# BEP31_Test_Interface4_Seed.net
KiCad netlist of a schematic drawn in EAGLE
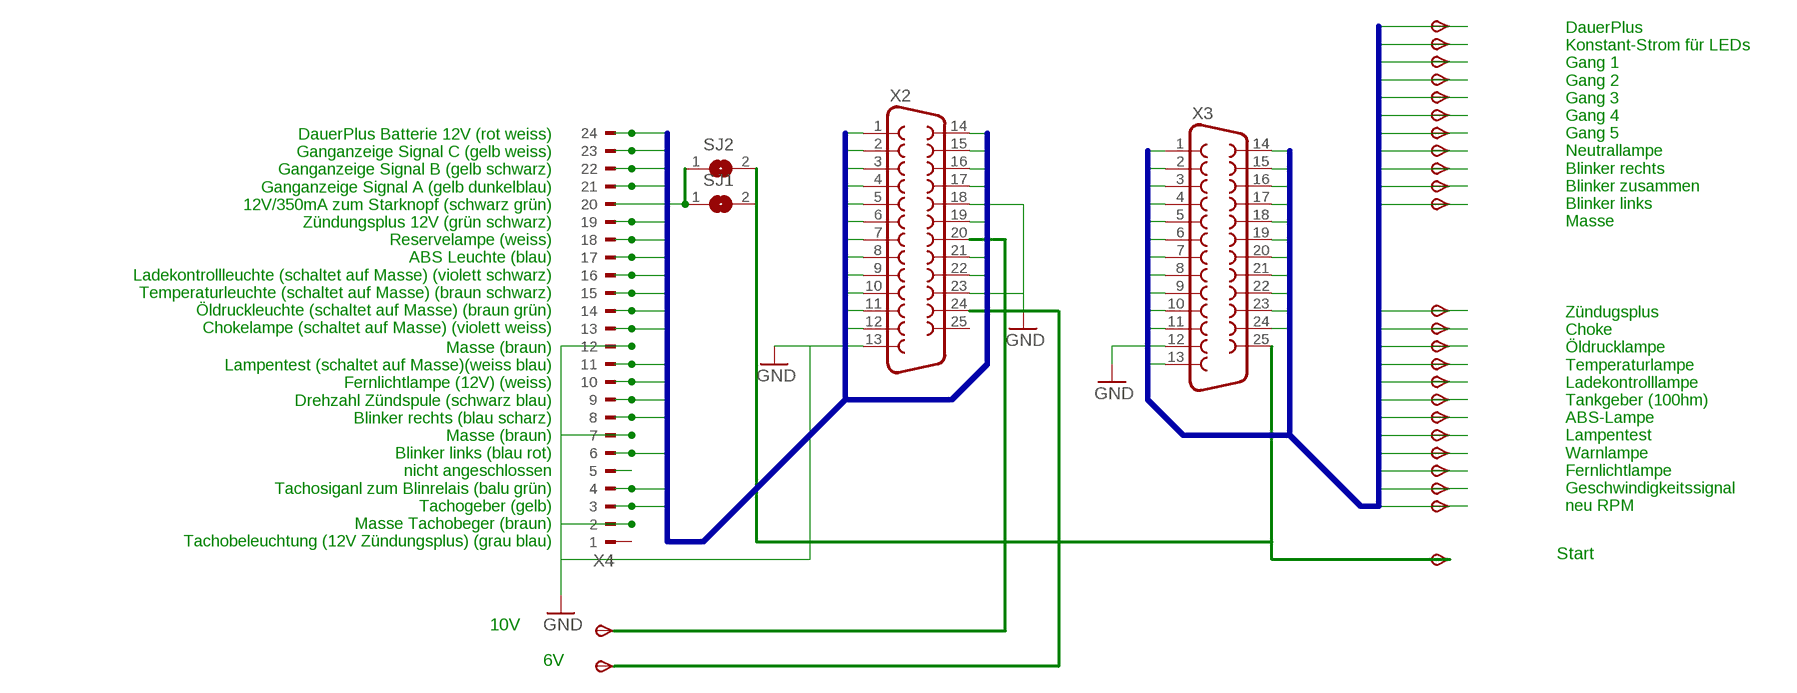
[diagram p0: schematic, sheet 1]
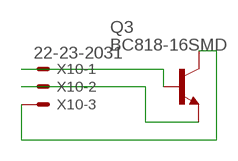
[diagram p1: schematic, sheet 2]
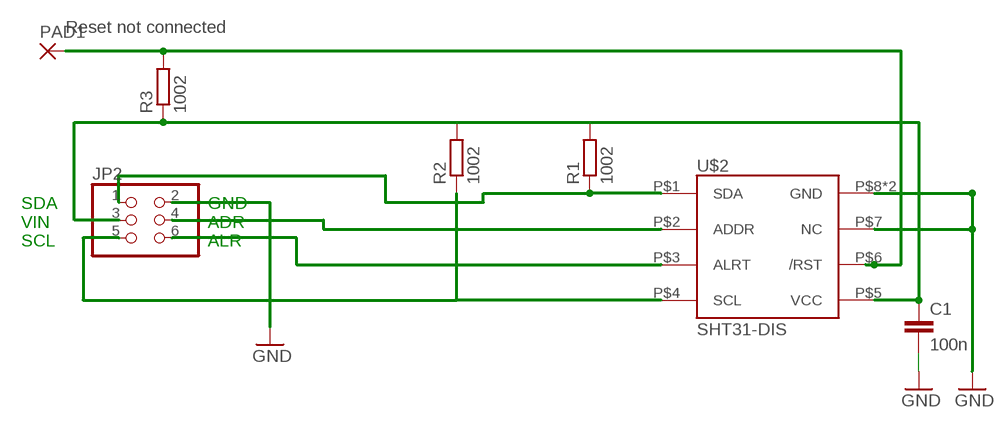
[diagram p2: schematic, sheet 3]

(export (version "E")
  (design (tool "Eeschema 10.0.6"))
  (components
    (comp (ref "Q3")
      (value "BC818-16SMD")
      (footprint "eagle-import:SOT23-BEC")
      (libsource (lib "eagle-import") (part "BC818SMD-16"))
    )
    (comp (ref "X10")
      (value "22-23-2031")
      (footprint "eagle-import:22-23-2031")
      (fields (field (name "MF") "MOLEX"))
      (libsource (lib "eagle-import") (part "22-23-2031"))
    )
    (comp (ref "C1")
      (value "100n")
      (footprint "eagle-import:C0805K")
      (libsource (lib "eagle-import") (part "C-EUC0805K"))
    )
    (comp (ref "JP2")
      (value "PINHD-2X3")
      (footprint "eagle-import:2X03")
      (libsource (lib "eagle-import") (part "PINHD-2X3"))
    )
    (comp (ref "PAD1")
      (value "1,6/0,8")
      (footprint "eagle-import:1,6_0,8")
      (libsource (lib "eagle-import") (part "1,6/0,8"))
    )
    (comp (ref "R1")
      (value "1002")
      (footprint "eagle-import:R0805")
      (libsource (lib "eagle-import") (part "R-EU_R0805"))
    )
    (comp (ref "R2")
      (value "1002")
      (footprint "eagle-import:R0805")
      (libsource (lib "eagle-import") (part "R-EU_R0805"))
    )
    (comp (ref "R3")
      (value "1002")
      (footprint "eagle-import:R0805")
      (libsource (lib "eagle-import") (part "R-EU_R0805"))
    )
    (comp (ref "U$2")
      (value "SHT31-DIS")
      (footprint "eagle-import:SHT3X")
      (libsource (lib "eagle-import") (part "SHT31-DIS"))
    )
    (comp (ref "SJ1") (value "SJ") (footprint "eagle-import:SJ") (libsource (lib "eagle-import") (part "SJ")))
    (comp (ref "SJ2") (value "SJ") (footprint "eagle-import:SJ") (libsource (lib "eagle-import") (part "SJ")))
    (comp (ref "TP1")
      (value "TPSFEDERPIN")
      (footprint "eagle-import:1,36ID")
      (libsource (lib "eagle-import") (part "TPSFEDERPIN"))
    )
    (comp (ref "TP2")
      (value "TPSFEDERPIN")
      (footprint "eagle-import:1,36ID")
      (libsource (lib "eagle-import") (part "TPSFEDERPIN"))
    )
    (comp (ref "TP3")
      (value "TPSFEDERPIN")
      (footprint "eagle-import:1,36ID")
      (libsource (lib "eagle-import") (part "TPSFEDERPIN"))
    )
    (comp (ref "TP4")
      (value "TPSFEDERPIN")
      (footprint "eagle-import:1,36ID")
      (libsource (lib "eagle-import") (part "TPSFEDERPIN"))
    )
    (comp (ref "TP5")
      (value "TPSFEDERPIN")
      (footprint "eagle-import:1,36ID")
      (libsource (lib "eagle-import") (part "TPSFEDERPIN"))
    )
    (comp (ref "TP6")
      (value "TPSFEDERPIN")
      (footprint "eagle-import:1,36ID")
      (libsource (lib "eagle-import") (part "TPSFEDERPIN"))
    )
    (comp (ref "TP7")
      (value "TPSFEDERPIN")
      (footprint "eagle-import:1,36ID")
      (libsource (lib "eagle-import") (part "TPSFEDERPIN"))
    )
    (comp (ref "TP8")
      (value "TPSFEDERPIN")
      (footprint "eagle-import:1,36ID")
      (libsource (lib "eagle-import") (part "TPSFEDERPIN"))
    )
    (comp (ref "TP9")
      (value "TPSFEDERPIN")
      (footprint "eagle-import:1,36ID")
      (libsource (lib "eagle-import") (part "TPSFEDERPIN"))
    )
    (comp (ref "TP10")
      (value "TPSFEDERPIN")
      (footprint "eagle-import:1,36ID")
      (libsource (lib "eagle-import") (part "TPSFEDERPIN"))
    )
    (comp (ref "TP11")
      (value "TPSFEDERPIN")
      (footprint "eagle-import:1,36ID")
      (libsource (lib "eagle-import") (part "TPSFEDERPIN"))
    )
    (comp (ref "TP12")
      (value "TPSFEDERPIN")
      (footprint "eagle-import:1,36ID")
      (libsource (lib "eagle-import") (part "TPSFEDERPIN"))
    )
    (comp (ref "TP13")
      (value "TPSFEDERPIN")
      (footprint "eagle-import:1,36ID")
      (libsource (lib "eagle-import") (part "TPSFEDERPIN"))
    )
    (comp (ref "TP14")
      (value "TPSFEDERPIN")
      (footprint "eagle-import:1,36ID")
      (libsource (lib "eagle-import") (part "TPSFEDERPIN"))
    )
    (comp (ref "TP15_10V")
      (value "TPSFEDERPIN")
      (footprint "eagle-import:1,36ID")
      (libsource (lib "eagle-import") (part "TPSFEDERPIN"))
    )
    (comp (ref "TP16")
      (value "TPSFEDERPIN")
      (footprint "eagle-import:1,36ID")
      (libsource (lib "eagle-import") (part "TPSFEDERPIN"))
    )
    (comp (ref "TP17")
      (value "TPSFEDERPIN")
      (footprint "eagle-import:1,36ID")
      (libsource (lib "eagle-import") (part "TPSFEDERPIN"))
    )
    (comp (ref "TP18")
      (value "TPSFEDERPIN")
      (footprint "eagle-import:1,36ID")
      (libsource (lib "eagle-import") (part "TPSFEDERPIN"))
    )
    (comp (ref "TP19")
      (value "TPSFEDERPIN")
      (footprint "eagle-import:1,36ID")
      (libsource (lib "eagle-import") (part "TPSFEDERPIN"))
    )
    (comp (ref "TP20_6V")
      (value "TPSFEDERPIN")
      (footprint "eagle-import:1,36ID")
      (libsource (lib "eagle-import") (part "TPSFEDERPIN"))
    )
    (comp (ref "TP21")
      (value "TPSFEDERPIN")
      (footprint "eagle-import:1,36ID")
      (libsource (lib "eagle-import") (part "TPSFEDERPIN"))
    )
    (comp (ref "TP22")
      (value "TPSFEDERPIN")
      (footprint "eagle-import:1,36ID")
      (libsource (lib "eagle-import") (part "TPSFEDERPIN"))
    )
    (comp (ref "TP23")
      (value "TPSFEDERPIN")
      (footprint "eagle-import:1,36ID")
      (libsource (lib "eagle-import") (part "TPSFEDERPIN"))
    )
    (comp (ref "TP24")
      (value "TPSFEDERPIN")
      (footprint "eagle-import:1,36ID")
      (libsource (lib "eagle-import") (part "TPSFEDERPIN"))
    )
    (comp (ref "TP25")
      (value "TPSFEDERPIN")
      (footprint "eagle-import:1,36ID")
      (libsource (lib "eagle-import") (part "TPSFEDERPIN"))
    )
    (comp (ref "TP26")
      (value "TPSFEDERPIN")
      (footprint "eagle-import:1,36ID")
      (libsource (lib "eagle-import") (part "TPSFEDERPIN"))
    )
    (comp (ref "X2")
      (value "F25H")
      (footprint "eagle-import:F25H")
      (libsource (lib "eagle-import") (part "F25H"))
    )
    (comp (ref "X3")
      (value "F25H")
      (footprint "eagle-import:F25H")
      (libsource (lib "eagle-import") (part "F25H"))
    )
    (comp (ref "X4")
      (value "CON_BMWTESTPINS")
      (footprint "eagle-import:24-TESTPIN_1,36ID")
      (libsource (lib "eagle-import") (part "CON_BMWTESTPINS"))
    )
  )
  (nets
    (net (code "1") (name "BMW1") (class "Default")
      (node (ref "X2") (pin "1") (pinfunction "1_1") (pintype "passive"))
      (node (ref "X4") (pin "P24") (pinfunction "24_P24") (pintype "passive"))
    )
    (net (code "2") (name "BMW2") (class "Default")
      (node (ref "X2") (pin "2") (pinfunction "2_2") (pintype "passive"))
      (node (ref "X4") (pin "P23") (pinfunction "23_P23") (pintype "passive"))
    )
    (net (code "3") (name "BMW3") (class "Default")
      (node (ref "X2") (pin "3") (pinfunction "3_3") (pintype "passive"))
      (node (ref "X4") (pin "P22") (pinfunction "22_P22") (pintype "passive"))
    )
    (net (code "4") (name "BMW4") (class "Default")
      (node (ref "X2") (pin "4") (pinfunction "4_4") (pintype "passive"))
      (node (ref "X4") (pin "P21") (pinfunction "21_P21") (pintype "passive"))
    )
    (net (code "5") (name "BMW5") (class "Default")
      (node (ref "SJ1") (pin "1") (pinfunction "1_1") (pintype "passive"))
      (node (ref "SJ2") (pin "1") (pinfunction "1_1") (pintype "passive"))
      (node (ref "X2") (pin "5") (pinfunction "5_5") (pintype "passive"))
      (node (ref "X4") (pin "P20") (pinfunction "20_P20") (pintype "passive"))
    )
    (net (code "6") (name "BMW6") (class "Default")
      (node (ref "X2") (pin "6") (pinfunction "6_6") (pintype "passive"))
      (node (ref "X4") (pin "P19") (pinfunction "19_P19") (pintype "passive"))
    )
    (net (code "7") (name "BMW7") (class "Default")
      (node (ref "X2") (pin "7") (pinfunction "7_7") (pintype "passive"))
      (node (ref "X4") (pin "P18") (pinfunction "18_P18") (pintype "passive"))
    )
    (net (code "8") (name "BMW8") (class "Default")
      (node (ref "X2") (pin "8") (pinfunction "8_8") (pintype "passive"))
      (node (ref "X4") (pin "P17") (pinfunction "17_P17") (pintype "passive"))
    )
    (net (code "9") (name "BMW9") (class "Default")
      (node (ref "X2") (pin "9") (pinfunction "9_9") (pintype "passive"))
      (node (ref "X4") (pin "P16") (pinfunction "16_P16") (pintype "passive"))
    )
    (net (code "10") (name "BMW10") (class "Default")
      (node (ref "X2") (pin "10") (pinfunction "10_10") (pintype "passive"))
      (node (ref "X4") (pin "P15") (pinfunction "15_P15") (pintype "passive"))
    )
    (net (code "11") (name "BMW11") (class "Default")
      (node (ref "X2") (pin "11") (pinfunction "11_11") (pintype "passive"))
      (node (ref "X4") (pin "P14") (pinfunction "14_P14") (pintype "passive"))
    )
    (net (code "12") (name "BMW12") (class "Default")
      (node (ref "X2") (pin "12") (pinfunction "12_12") (pintype "passive"))
      (node (ref "X4") (pin "P13") (pinfunction "13_P13") (pintype "passive"))
    )
    (net (code "13") (name "BMW14") (class "Default")
      (node (ref "X2") (pin "14") (pinfunction "14_14") (pintype "passive"))
      (node (ref "X4") (pin "P11") (pinfunction "11_P11") (pintype "passive"))
    )
    (net (code "14") (name "BMW15") (class "Default")
      (node (ref "X2") (pin "15") (pinfunction "15_15") (pintype "passive"))
      (node (ref "X4") (pin "P10") (pinfunction "10_P10") (pintype "passive"))
    )
    (net (code "15") (name "BMW16") (class "Default")
      (node (ref "X2") (pin "16") (pinfunction "16_16") (pintype "passive"))
      (node (ref "X4") (pin "P9") (pinfunction "9_P9") (pintype "passive"))
    )
    (net (code "16") (name "BMW17") (class "Default")
      (node (ref "X2") (pin "17") (pinfunction "17_17") (pintype "passive"))
      (node (ref "X4") (pin "P8") (pinfunction "8_P8") (pintype "passive"))
    )
    (net (code "17") (name "BMW19") (class "Default")
      (node (ref "X2") (pin "19") (pinfunction "19_19") (pintype "passive"))
      (node (ref "X4") (pin "P6") (pinfunction "6_P6") (pintype "passive"))
    )
    (net (code "18") (name "BMW21") (class "Default")
      (node (ref "X2") (pin "21") (pinfunction "21_21") (pintype "passive"))
      (node (ref "X4") (pin "P4") (pinfunction "4_P4") (pintype "passive"))
    )
    (net (code "19") (name "BMW22") (class "Default")
      (node (ref "X2") (pin "22") (pinfunction "22_22") (pintype "passive"))
      (node (ref "X4") (pin "P3") (pinfunction "3_P3") (pintype "passive"))
    )
    (net (code "20") (name "GND") (class "Default")
      (node (ref "C1") (pin "2") (pinfunction "2_2") (pintype "passive"))
      (node (ref "JP2") (pin "2") (pinfunction "2_2") (pintype "passive"))
      (node (ref "U$2") (pin "P$7") (pinfunction "NC_P$7") (pintype "bidirectional"))
      (node (ref "U$2") (pin "P$8") (pinfunction "GND_P$8") (pintype "bidirectional"))
      (node (ref "U$2") (pin "PAD") (pinfunction "GND_PAD") (pintype "bidirectional"))
      (node (ref "X2") (pin "13") (pinfunction "13_13") (pintype "passive"))
      (node (ref "X2") (pin "18") (pinfunction "18_18") (pintype "passive"))
      (node (ref "X2") (pin "23") (pinfunction "23_23") (pintype "passive"))
      (node (ref "X3") (pin "12") (pinfunction "12_12") (pintype "passive"))
      (node (ref "X4") (pin "P12") (pinfunction "12_P12") (pintype "passive"))
      (node (ref "X4") (pin "P2") (pinfunction "2_P2") (pintype "passive"))
      (node (ref "X4") (pin "P7") (pinfunction "7_P7") (pintype "passive"))
    )
    (net (code "21") (name "Net-(PAD1-P)") (class "Default")
      (node (ref "PAD1") (pin "1") (pinfunction "P_1") (pintype "passive"))
      (node (ref "R3") (pin "2") (pinfunction "2_2") (pintype "passive"))
      (node (ref "U$2") (pin "P$6") (pinfunction "/RST_P$6") (pintype "bidirectional"))
    )
    (net (code "22") (name "Net-(TP14-PP)") (class "Default")
      (node (ref "SJ1") (pin "2") (pinfunction "2_2") (pintype "passive"))
      (node (ref "SJ2") (pin "2") (pinfunction "2_2") (pintype "passive"))
      (node (ref "TP14") (pin "P$1") (pinfunction "PP_P$1") (pintype "input"))
      (node (ref "X3") (pin "25") (pinfunction "25_25") (pintype "passive"))
    )
    (net (code "23") (name "Net-(TP15_10V-PP)") (class "Default")
      (node (ref "TP15_10V") (pin "P$1") (pinfunction "PP_P$1") (pintype "input"))
      (node (ref "X2") (pin "20") (pinfunction "20_20") (pintype "passive"))
    )
    (net (code "24") (name "Net-(TP20_6V-PP)") (class "Default")
      (node (ref "TP20_6V") (pin "P$1") (pinfunction "PP_P$1") (pintype "input"))
      (node (ref "X2") (pin "24") (pinfunction "24_24") (pintype "passive"))
    )
    (net (code "25") (name "Net-(U$2-ADDR)") (class "Default")
      (node (ref "JP2") (pin "4") (pinfunction "4_4") (pintype "passive"))
      (node (ref "U$2") (pin "P$2") (pinfunction "ADDR_P$2") (pintype "bidirectional"))
    )
    (net (code "26") (name "Net-(U$2-ALRT)") (class "Default")
      (node (ref "JP2") (pin "6") (pinfunction "6_6") (pintype "passive"))
      (node (ref "U$2") (pin "P$3") (pinfunction "ALRT_P$3") (pintype "bidirectional"))
    )
    (net (code "27") (name "Net-(U$2-SCL)") (class "Default")
      (node (ref "JP2") (pin "5") (pinfunction "5_5") (pintype "passive"))
      (node (ref "R2") (pin "1") (pinfunction "1_1") (pintype "passive"))
      (node (ref "U$2") (pin "P$4") (pinfunction "SCL_P$4") (pintype "bidirectional"))
    )
    (net (code "28") (name "Net-(U$2-SDA)") (class "Default")
      (node (ref "JP2") (pin "1") (pinfunction "1_1") (pintype "passive"))
      (node (ref "R1") (pin "1") (pinfunction "1_1") (pintype "passive"))
      (node (ref "U$2") (pin "P$1") (pinfunction "SDA_P$1") (pintype "bidirectional"))
    )
    (net (code "29") (name "Net-(U$2-VCC)") (class "Default")
      (node (ref "C1") (pin "1") (pinfunction "1_1") (pintype "passive"))
      (node (ref "JP2") (pin "3") (pinfunction "3_3") (pintype "passive"))
      (node (ref "R1") (pin "2") (pinfunction "2_2") (pintype "passive"))
      (node (ref "R2") (pin "2") (pinfunction "2_2") (pintype "passive"))
      (node (ref "R3") (pin "1") (pinfunction "1_1") (pintype "passive"))
      (node (ref "U$2") (pin "P$5") (pinfunction "VCC_P$5") (pintype "bidirectional"))
    )
    (net (code "30") (name "Net-(X10A-S)") (class "Default")
      (node (ref "Q3") (pin "B") (pinfunction "B_B") (pintype "passive"))
      (node (ref "X10") (pin "1") (pinfunction "S_1") (pintype "passive"))
    )
    (net (code "31") (name "Net-(X10B-S)") (class "Default")
      (node (ref "Q3") (pin "E") (pinfunction "E_E") (pintype "passive"))
      (node (ref "X10") (pin "2") (pinfunction "S_2") (pintype "passive"))
    )
    (net (code "32") (name "Net-(X10C-S)") (class "Default")
      (node (ref "Q3") (pin "C") (pinfunction "C_C") (pintype "passive"))
      (node (ref "X10") (pin "3") (pinfunction "S_3") (pintype "passive"))
    )
    (net (code "33") (name "WAGO1") (class "Default")
      (node (ref "TP1") (pin "P$1") (pinfunction "PP_P$1") (pintype "input"))
      (node (ref "X3") (pin "1") (pinfunction "1_1") (pintype "passive"))
    )
    (net (code "34") (name "WAGO2") (class "Default")
      (node (ref "TP2") (pin "P$1") (pinfunction "PP_P$1") (pintype "input"))
      (node (ref "X3") (pin "2") (pinfunction "2_2") (pintype "passive"))
    )
    (net (code "35") (name "WAGO3") (class "Default")
      (node (ref "TP3") (pin "P$1") (pinfunction "PP_P$1") (pintype "input"))
      (node (ref "X3") (pin "3") (pinfunction "3_3") (pintype "passive"))
    )
    (net (code "36") (name "WAGO4") (class "Default")
      (node (ref "TP4") (pin "P$1") (pinfunction "PP_P$1") (pintype "input"))
      (node (ref "X3") (pin "4") (pinfunction "4_4") (pintype "passive"))
    )
    (net (code "37") (name "WAGO5") (class "Default")
      (node (ref "TP5") (pin "P$1") (pinfunction "PP_P$1") (pintype "input"))
      (node (ref "X3") (pin "5") (pinfunction "5_5") (pintype "passive"))
    )
    (net (code "38") (name "WAGO6") (class "Default")
      (node (ref "TP6") (pin "P$1") (pinfunction "PP_P$1") (pintype "input"))
      (node (ref "X3") (pin "6") (pinfunction "6_6") (pintype "passive"))
    )
    (net (code "39") (name "WAGO7") (class "Default")
      (node (ref "TP7") (pin "P$1") (pinfunction "PP_P$1") (pintype "input"))
      (node (ref "X3") (pin "7") (pinfunction "7_7") (pintype "passive"))
    )
    (net (code "40") (name "WAGO8") (class "Default")
      (node (ref "TP8") (pin "P$1") (pinfunction "PP_P$1") (pintype "input"))
      (node (ref "X3") (pin "8") (pinfunction "8_8") (pintype "passive"))
    )
    (net (code "41") (name "WAGO9") (class "Default")
      (node (ref "TP9") (pin "P$1") (pinfunction "PP_P$1") (pintype "input"))
      (node (ref "X3") (pin "9") (pinfunction "9_9") (pintype "passive"))
    )
    (net (code "42") (name "WAGO10") (class "Default")
      (node (ref "TP10") (pin "P$1") (pinfunction "PP_P$1") (pintype "input"))
      (node (ref "X3") (pin "10") (pinfunction "10_10") (pintype "passive"))
    )
    (net (code "43") (name "WAGO11") (class "Default")
      (node (ref "TP11") (pin "P$1") (pinfunction "PP_P$1") (pintype "input"))
      (node (ref "X3") (pin "11") (pinfunction "11_11") (pintype "passive"))
    )
    (net (code "44") (name "WAGO13") (class "Default")
      (node (ref "TP12") (pin "P$1") (pinfunction "PP_P$1") (pintype "input"))
      (node (ref "X3") (pin "13") (pinfunction "13_13") (pintype "passive"))
    )
    (net (code "45") (name "WAGO14") (class "Default")
      (node (ref "TP16") (pin "P$1") (pinfunction "PP_P$1") (pintype "input"))
      (node (ref "X3") (pin "14") (pinfunction "14_14") (pintype "passive"))
    )
    (net (code "46") (name "WAGO15") (class "Default")
      (node (ref "TP17") (pin "P$1") (pinfunction "PP_P$1") (pintype "input"))
      (node (ref "X3") (pin "15") (pinfunction "15_15") (pintype "passive"))
    )
    (net (code "47") (name "WAGO16") (class "Default")
      (node (ref "TP18") (pin "P$1") (pinfunction "PP_P$1") (pintype "input"))
      (node (ref "X3") (pin "16") (pinfunction "16_16") (pintype "passive"))
    )
    (net (code "48") (name "WAGO17") (class "Default")
      (node (ref "TP19") (pin "P$1") (pinfunction "PP_P$1") (pintype "input"))
      (node (ref "X3") (pin "17") (pinfunction "17_17") (pintype "passive"))
    )
    (net (code "49") (name "WAGO18") (class "Default")
      (node (ref "TP21") (pin "P$1") (pinfunction "PP_P$1") (pintype "input"))
      (node (ref "X3") (pin "18") (pinfunction "18_18") (pintype "passive"))
    )
    (net (code "50") (name "WAGO19") (class "Default")
      (node (ref "TP22") (pin "P$1") (pinfunction "PP_P$1") (pintype "input"))
      (node (ref "X3") (pin "19") (pinfunction "19_19") (pintype "passive"))
    )
    (net (code "51") (name "WAGO20") (class "Default")
      (node (ref "TP23") (pin "P$1") (pinfunction "PP_P$1") (pintype "input"))
      (node (ref "X3") (pin "20") (pinfunction "20_20") (pintype "passive"))
    )
    (net (code "52") (name "WAGO21") (class "Default")
      (node (ref "TP24") (pin "P$1") (pinfunction "PP_P$1") (pintype "input"))
      (node (ref "X3") (pin "21") (pinfunction "21_21") (pintype "passive"))
    )
    (net (code "53") (name "WAGO22") (class "Default")
      (node (ref "TP25") (pin "P$1") (pinfunction "PP_P$1") (pintype "input"))
      (node (ref "X3") (pin "22") (pinfunction "22_22") (pintype "passive"))
    )
    (net (code "54") (name "WAGO23") (class "Default")
      (node (ref "TP26") (pin "P$1") (pinfunction "PP_P$1") (pintype "input"))
      (node (ref "X3") (pin "23") (pinfunction "23_23") (pintype "passive"))
    )
    (net (code "55") (name "WAGO24") (class "Default")
      (node (ref "TP13") (pin "P$1") (pinfunction "PP_P$1") (pintype "input"))
      (node (ref "X3") (pin "24") (pinfunction "24_24") (pintype "passive"))
    )
    (net (code "56") (name "unconnected-(X2-Pad25)") (class "Default")
      (node (ref "X2") (pin "25") (pinfunction "25_25") (pintype "passive"))
    )
    (net (code "57") (name "unconnected-(X4-1-PadP1)") (class "Default")
      (node (ref "X4") (pin "P1") (pinfunction "1_P1") (pintype "passive"))
    )
    (net (code "58") (name "unconnected-(X4-5-PadP5)") (class "Default")
      (node (ref "X4") (pin "P5") (pinfunction "5_P5") (pintype "passive"))
    )
  )
)
